# Attempt_1.net
KiCad netlist of a schematic drawn in EAGLE
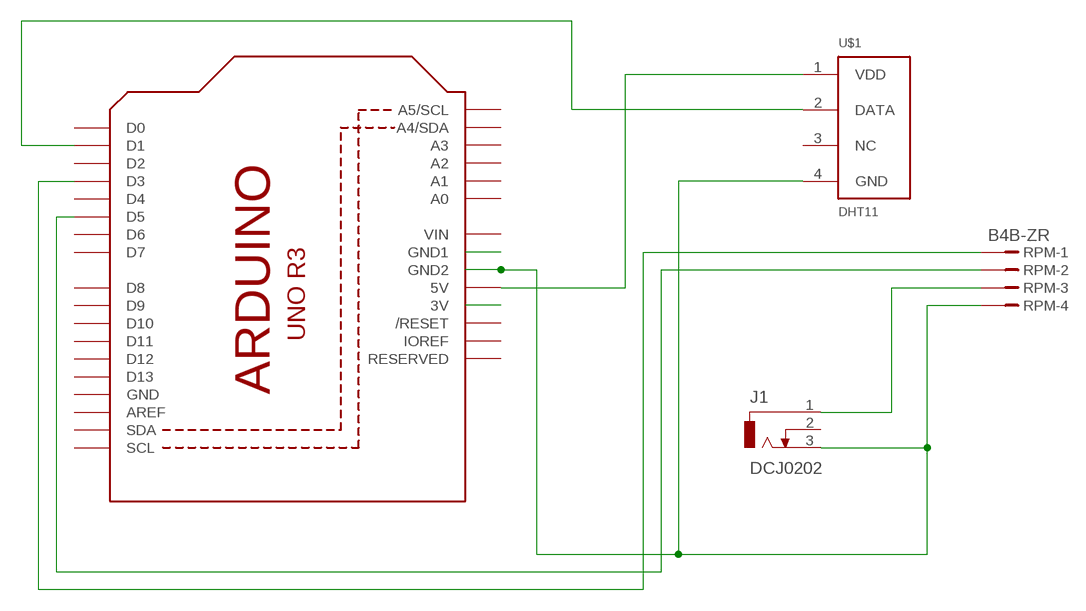
[diagram p0: schematic, sheet 1]

(export (version "E")
  (design (tool "Eeschema 10.0.6"))
  (components
    (comp (ref "J1")
      (value "DCJ0202")
      (footprint "eagle-import:DCJ0202")
      (libsource (lib "eagle-import") (part "DCJ0202"))
    )
    (comp (ref "RPM")
      (value "B4B-ZR")
      (footprint "eagle-import:B4B-ZR")
      (fields (field (name "MF") "FARNELL") (field (name "MPN") "B4B-ZR(LF)(SN)"))
      (libsource (lib "eagle-import") (part "?4B-ZRB"))
    )
    (comp (ref "U$1")
      (value "DHT11")
      (footprint "eagle-import:DHT11")
      (libsource (lib "eagle-import") (part "DHT11"))
    )
    (comp (ref "U1")
      (value "ARDUINOR3-BPLACE")
      (footprint "eagle-import:ARDUINOR3-BPLACE")
      (libsource (lib "eagle-import") (part "ARDUINOR3-BPLACE"))
    )
  )
  (nets
    (net (code "1") (name "/GND") (class "Default")
      (node (ref "U1") (pin "GND") (pinfunction "GND_GND") (pintype "power_in"))
    )
    (net (code "2") (name "/VIN") (class "Default")
      (node (ref "U1") (pin "VIN") (pinfunction "VIN_VIN") (pintype "power_in"))
    )
    (net (code "3") (name "Net-(RPM-Pad1)") (class "Default")
      (node (ref "RPM") (pin "1") (pinfunction "1_1") (pintype "passive"))
      (node (ref "U1") (pin "D3") (pinfunction "D3_D3") (pintype "bidirectional"))
    )
    (net (code "4") (name "Net-(RPMB-1)") (class "Default")
      (node (ref "RPM") (pin "2") (pinfunction "1_2") (pintype "passive"))
      (node (ref "U1") (pin "D5") (pinfunction "D5_D5") (pintype "bidirectional"))
    )
    (net (code "5") (name "Net-(RPMC-1)") (class "Default")
      (node (ref "J1") (pin "1") (pinfunction "1_1") (pintype "passive"))
      (node (ref "RPM") (pin "3") (pinfunction "1_3") (pintype "passive"))
    )
    (net (code "6") (name "Net-(RPMD-1)") (class "Default")
      (node (ref "J1") (pin "3") (pinfunction "3_3") (pintype "passive"))
      (node (ref "RPM") (pin "4") (pinfunction "1_4") (pintype "passive"))
      (node (ref "U$1") (pin "4") (pinfunction "GND_4") (pintype "power_in"))
      (node (ref "U1") (pin "GND2") (pinfunction "GND2_GND2") (pintype "power_in"))
    )
    (net (code "7") (name "Net-(U$1-DATA)") (class "Default")
      (node (ref "U$1") (pin "2") (pinfunction "DATA_2") (pintype "bidirectional"))
      (node (ref "U1") (pin "D1") (pinfunction "D1_D1") (pintype "bidirectional"))
    )
    (net (code "8") (name "Net-(U$1-VDD)") (class "Default")
      (node (ref "U$1") (pin "1") (pinfunction "VDD_1") (pintype "power_in"))
      (node (ref "U1") (pin "5V") (pinfunction "5V_5V") (pintype "power_in"))
    )
    (net (code "9") (name "unconnected-(J1-Pad2)") (class "Default")
      (node (ref "J1") (pin "2") (pinfunction "2_2") (pintype "passive"))
    )
    (net (code "10") (name "unconnected-(U$1-NC-Pad3)") (class "Default")
      (node (ref "U$1") (pin "3") (pinfunction "NC_3") (pintype "bidirectional"))
    )
    (net (code "11") (name "unconnected-(U1-A4{slash}SDA-PadA4)") (class "Default")
      (node (ref "U1") (pin "A4") (pinfunction "A4/SDA_A4") (pintype "bidirectional"))
    )
    (net (code "12") (name "unconnected-(U1-A5{slash}SCL-PadA5)") (class "Default")
      (node (ref "U1") (pin "A5") (pinfunction "A5/SCL_A5") (pintype "bidirectional"))
    )
    (net (code "13") (name "unconnected-(U1-Pad3V)") (class "Default")
      (node (ref "U1") (pin "3V") (pinfunction "3V_3V") (pintype "power_in"))
    )
    (net (code "14") (name "unconnected-(U1-PadA0)") (class "Default")
      (node (ref "U1") (pin "A0") (pinfunction "A0_A0") (pintype "bidirectional"))
    )
    (net (code "15") (name "unconnected-(U1-PadA1)") (class "Default")
      (node (ref "U1") (pin "A1") (pinfunction "A1_A1") (pintype "bidirectional"))
    )
    (net (code "16") (name "unconnected-(U1-PadA2)") (class "Default")
      (node (ref "U1") (pin "A2") (pinfunction "A2_A2") (pintype "bidirectional"))
    )
    (net (code "17") (name "unconnected-(U1-PadA3)") (class "Default")
      (node (ref "U1") (pin "A3") (pinfunction "A3_A3") (pintype "bidirectional"))
    )
    (net (code "18") (name "unconnected-(U1-PadAREF)") (class "Default")
      (node (ref "U1") (pin "AREF") (pinfunction "AREF_AREF") (pintype "bidirectional"))
    )
    (net (code "19") (name "unconnected-(U1-PadD0)") (class "Default")
      (node (ref "U1") (pin "D0") (pinfunction "D0_D0") (pintype "bidirectional"))
    )
    (net (code "20") (name "unconnected-(U1-PadD2)") (class "Default")
      (node (ref "U1") (pin "D2") (pinfunction "D2_D2") (pintype "bidirectional"))
    )
    (net (code "21") (name "unconnected-(U1-PadD4)") (class "Default")
      (node (ref "U1") (pin "D4") (pinfunction "D4_D4") (pintype "bidirectional"))
    )
    (net (code "22") (name "unconnected-(U1-PadD6)") (class "Default")
      (node (ref "U1") (pin "D6") (pinfunction "D6_D6") (pintype "bidirectional"))
    )
    (net (code "23") (name "unconnected-(U1-PadD7)") (class "Default")
      (node (ref "U1") (pin "D7") (pinfunction "D7_D7") (pintype "bidirectional"))
    )
    (net (code "24") (name "unconnected-(U1-PadD8)") (class "Default")
      (node (ref "U1") (pin "D8") (pinfunction "D8_D8") (pintype "bidirectional"))
    )
    (net (code "25") (name "unconnected-(U1-PadD9)") (class "Default")
      (node (ref "U1") (pin "D9") (pinfunction "D9_D9") (pintype "bidirectional"))
    )
    (net (code "26") (name "unconnected-(U1-PadD10)") (class "Default")
      (node (ref "U1") (pin "D10") (pinfunction "D10_D10") (pintype "bidirectional"))
    )
    (net (code "27") (name "unconnected-(U1-PadD11)") (class "Default")
      (node (ref "U1") (pin "D11") (pinfunction "D11_D11") (pintype "bidirectional"))
    )
    (net (code "28") (name "unconnected-(U1-PadD12)") (class "Default")
      (node (ref "U1") (pin "D12") (pinfunction "D12_D12") (pintype "bidirectional"))
    )
    (net (code "29") (name "unconnected-(U1-PadD13)") (class "Default")
      (node (ref "U1") (pin "D13") (pinfunction "D13_D13") (pintype "bidirectional"))
    )
    (net (code "30") (name "unconnected-(U1-PadGND1)") (class "Default")
      (node (ref "U1") (pin "GND1") (pinfunction "GND1_GND1") (pintype "power_in"))
    )
    (net (code "31") (name "unconnected-(U1-PadIOREF)") (class "Default")
      (node (ref "U1") (pin "IOREF") (pinfunction "IOREF_IOREF") (pintype "output"))
    )
    (net (code "32") (name "unconnected-(U1-PadRESERVED)") (class "Default")
      (node (ref "U1") (pin "RESERVED") (pinfunction "RESERVED_RESERVED") (pintype "no_connect"))
    )
    (net (code "33") (name "unconnected-(U1-PadSCL)") (class "Default")
      (node (ref "U1") (pin "SCL") (pinfunction "SCL_SCL") (pintype "bidirectional"))
    )
    (net (code "34") (name "unconnected-(U1-PadSDA)") (class "Default")
      (node (ref "U1") (pin "SDA") (pinfunction "SDA_SDA") (pintype "bidirectional"))
    )
    (net (code "35") (name "unconnected-(U1-{slash}RESET-PadRESET)") (class "Default")
      (node (ref "U1") (pin "RESET") (pinfunction "/RESET_RESET") (pintype "bidirectional"))
    )
  )
)
